# Peripheral_Connections.net
KiCad netlist of a schematic drawn in Altium Designer
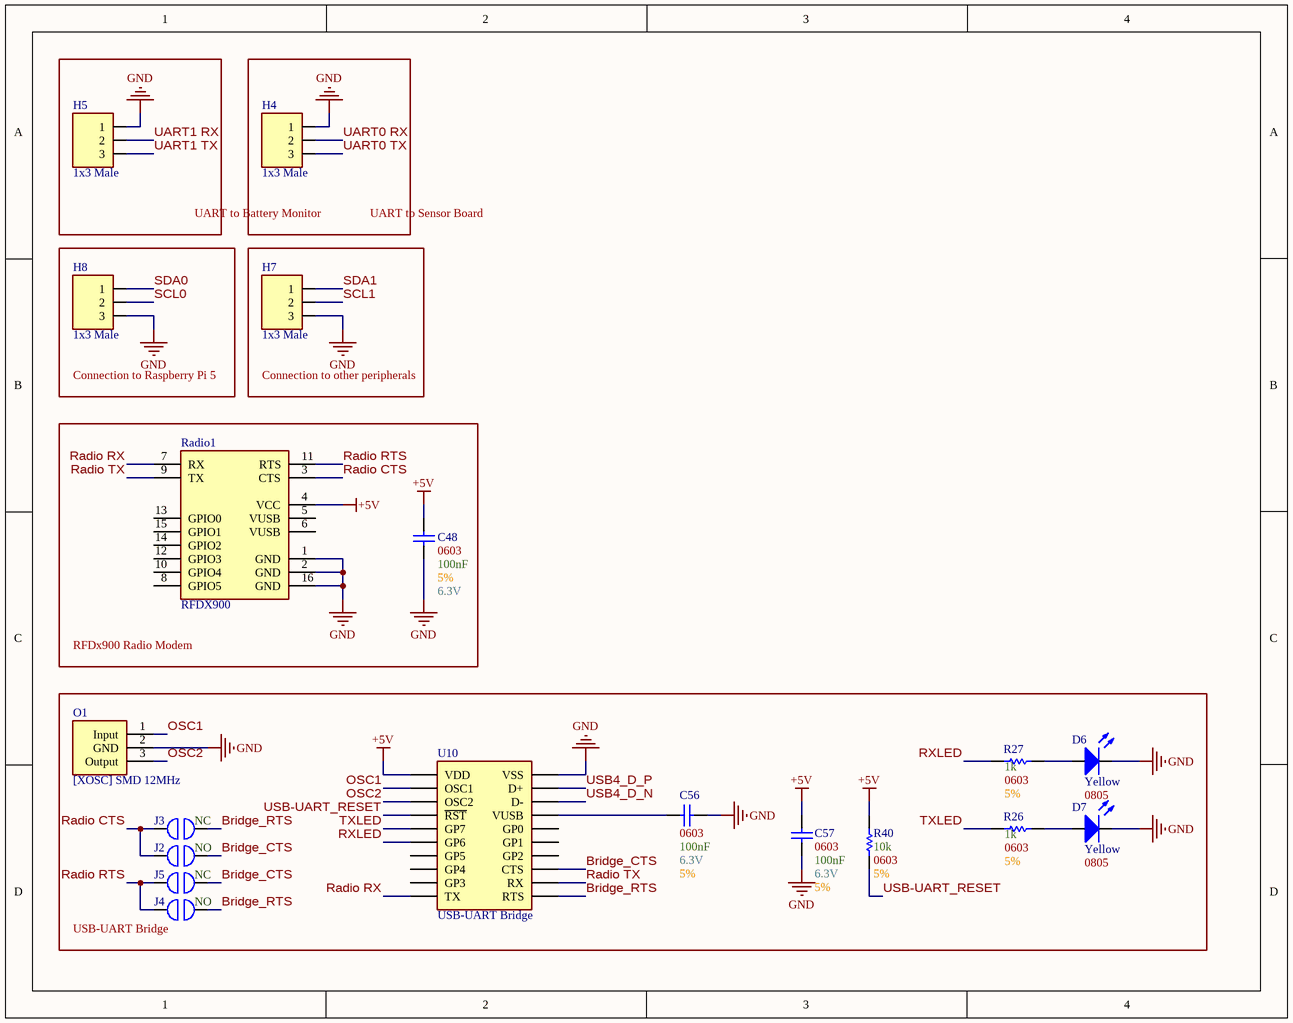
[diagram p0: Peripheral Connections.SchDoc]

(export (version "E")
  (design (tool "Eeschema 10.0.6"))
  (components
    (comp (ref "C48")
      (value "[Cap] SMD Nonpolarized")
      (footprint "[Cap] SMD 0603")
      (fields
        (field (name "SIZE PACKAGE") "0603")
        (field (name "CAPACITANCE") "100nF")
        (field (name "VOLTAGE") "6.3V")
        (field (name "TOLERANCE") "5%")
      )
      (libsource (lib "RADM Components") (part "[Cap] SMD Nonpolarized"))
    )
    (comp (ref "C56")
      (value "[Cap] SMD Nonpolarized")
      (footprint "[Cap] SMD 0603")
      (fields
        (field (name "SIZE PACKAGE") "0603")
        (field (name "CAPACITANCE") "100nF")
        (field (name "VOLTAGE") "6.3V")
        (field (name "TOLERANCE") "5%")
      )
      (libsource (lib "RADM Components") (part "[Cap] SMD Nonpolarized"))
    )
    (comp (ref "C57")
      (value "[Cap] SMD Nonpolarized")
      (footprint "[Cap] SMD 0603")
      (fields
        (field (name "SIZE PACKAGE") "0603")
        (field (name "CAPACITANCE") "100nF")
        (field (name "VOLTAGE") "6.3V")
        (field (name "TOLERANCE") "5%")
      )
      (libsource (lib "RADM Components") (part "[Cap] SMD Nonpolarized"))
    )
    (comp (ref "D6")
      (value "SMD LED")
      (footprint "[LED] SMD 0805")
      (description "Generic")
      (fields (field (name "COLOR") "Yellow") (field (name "SIZE PACKAGE") "0805"))
      (libsource (lib "RADM Components") (part "[LED] SMD"))
    )
    (comp (ref "D7")
      (value "SMD LED")
      (footprint "[LED] SMD 0805")
      (description "Generic")
      (fields (field (name "COLOR") "Yellow") (field (name "SIZE PACKAGE") "0805"))
      (libsource (lib "RADM Components") (part "[LED] SMD"))
    )
    (comp (ref "H4")
      (value "1x3 Male")
      (footprint "[Header] Shrouded 1x3 Male")
      (description "070543-0037\r\nMates with 005057-9403")
      (libsource (lib "RADM Connectors") (part "[Header] Shrouded 1x3 Male"))
    )
    (comp (ref "H5")
      (value "1x3 Male")
      (footprint "[Header] Shrouded 1x3 Male")
      (description "070543-0037\r\nMates with 005057-9403")
      (libsource (lib "RADM Connectors") (part "[Header] Shrouded 1x3 Male"))
    )
    (comp (ref "H7")
      (value "1x3 Male")
      (footprint "[Header] Shrouded 1x3 Male")
      (description "070543-0037\r\nMates with 005057-9403")
      (libsource (lib "RADM Connectors") (part "[Header] Shrouded 1x3 Male"))
    )
    (comp (ref "H8")
      (value "1x3 Male")
      (footprint "[Header] Shrouded 1x3 Male")
      (description "070543-0037\r\nMates with 005057-9403")
      (libsource (lib "RADM Connectors") (part "[Header] Shrouded 1x3 Male"))
    )
    (comp (ref "J2")
      (value "[Jump] SMD Jumper")
      (footprint "[Jumper] Solderable Jumper")
      (description "Solderable jumper")
      (fields (field (name "NO/NC") "NO"))
      (libsource (lib "RADM Components") (part "[Jump] SMD Jumper"))
    )
    (comp (ref "J3")
      (value "[Jump] SMD Jumper")
      (footprint "[Jumper] Solderable Jumper")
      (description "Solderable jumper")
      (fields (field (name "NO/NC") "NC"))
      (libsource (lib "RADM Components") (part "[Jump] SMD Jumper"))
    )
    (comp (ref "J4")
      (value "[Jump] SMD Jumper")
      (footprint "[Jumper] Solderable Jumper")
      (description "Solderable jumper")
      (fields (field (name "NO/NC") "NO"))
      (libsource (lib "RADM Components") (part "[Jump] SMD Jumper"))
    )
    (comp (ref "J5")
      (value "[Jump] SMD Jumper")
      (footprint "[Jumper] Solderable Jumper")
      (description "Solderable jumper")
      (fields (field (name "NO/NC") "NC"))
      (libsource (lib "RADM Components") (part "[Jump] SMD Jumper"))
    )
    (comp (ref "O1")
      (value "[XOSC] SMD 12MHz")
      (footprint "[XOSC] SMD 12MHz")
      (libsource (lib "RADM Components") (part "[XOSC] SMD 12MHz"))
    )
    (comp (ref "R26")
      (value "[Res] SMD Resistor")
      (footprint "[Res] SMD 0603")
      (description "Generic")
      (fields
        (field (name "RESISTANCE") "1k")
        (field (name "SIZE PACKAGE") "0603")
        (field (name "TOLERANCE") "5%")
      )
      (libsource (lib "RADM Components") (part "[Res] SMD Resistor"))
    )
    (comp (ref "R27")
      (value "[Res] SMD Resistor")
      (footprint "[Res] SMD 0603")
      (description "Generic")
      (fields
        (field (name "RESISTANCE") "1k")
        (field (name "SIZE PACKAGE") "0603")
        (field (name "TOLERANCE") "5%")
      )
      (libsource (lib "RADM Components") (part "[Res] SMD Resistor"))
    )
    (comp (ref "R40")
      (value "[Res] SMD Resistor")
      (footprint "[Res] SMD 0603")
      (description "Generic")
      (fields
        (field (name "RESISTANCE") "10k")
        (field (name "SIZE PACKAGE") "0603")
        (field (name "TOLERANCE") "5%")
      )
      (libsource (lib "RADM Components") (part "[Res] SMD Resistor"))
    )
    (comp (ref "Radio1")
      (value "RFDX900")
      (footprint "[Device] RFDX900 Radio SMD Mount")
      (description "RFDX900 Long-Range RF Module")
      (libsource (lib "RADM Components") (part "[Device] RFDX900 Radio"))
    )
    (comp (ref "U10")
      (value "USB-UART Bridge")
      (footprint "[IC] USB-UART Bridge")
      (description "MCP2200T-I/SO")
      (libsource (lib "RADM Components") (part "[IC] USB-UART Bridge"))
    )
  )
  (nets
    (net (code "1") (name "+5V") (class "Default")
      (node (ref "C48") (pin "2") (pinfunction "2_2") (pintype "passive"))
      (node (ref "C57") (pin "2") (pinfunction "2_2") (pintype "passive"))
      (node (ref "R40") (pin "2") (pinfunction "2_2") (pintype "passive"))
      (node (ref "Radio1") (pin "4") (pinfunction "VCC_4") (pintype "passive"))
      (node (ref "U10") (pin "1") (pinfunction "VDD_1") (pintype "passive"))
    )
    (net (code "2") (name "/Bridge_CTS") (class "Default")
      (node (ref "J2") (pin "2") (pintype "passive"))
      (node (ref "J5") (pin "2") (pintype "passive"))
      (node (ref "U10") (pin "13") (pinfunction "CTS_13") (pintype "passive"))
    )
    (net (code "3") (name "/Bridge_RTS") (class "Default")
      (node (ref "J3") (pin "2") (pintype "passive"))
      (node (ref "J4") (pin "2") (pintype "passive"))
      (node (ref "U10") (pin "11") (pinfunction "RTS_11") (pintype "passive"))
    )
    (net (code "4") (name "/OSC1") (class "Default")
      (node (ref "O1") (pin "1") (pinfunction "Input_1") (pintype "passive"))
      (node (ref "U10") (pin "2") (pinfunction "OSC1_2") (pintype "passive"))
    )
    (net (code "5") (name "/OSC2") (class "Default")
      (node (ref "O1") (pin "3") (pinfunction "Output_3") (pintype "passive"))
      (node (ref "U10") (pin "3") (pinfunction "OSC2_3") (pintype "passive"))
    )
    (net (code "6") (name "/RXLED") (class "Default")
      (node (ref "R27") (pin "2") (pinfunction "2_2") (pintype "passive"))
      (node (ref "U10") (pin "6") (pinfunction "GP6_6") (pintype "passive"))
    )
    (net (code "7") (name "/Radio CTS") (class "Default")
      (node (ref "J2") (pin "1") (pintype "passive"))
      (node (ref "J3") (pin "1") (pintype "passive"))
      (node (ref "Radio1") (pin "3") (pinfunction "CTS_3") (pintype "passive"))
    )
    (net (code "8") (name "/Radio RTS") (class "Default")
      (node (ref "J4") (pin "1") (pintype "passive"))
      (node (ref "J5") (pin "1") (pintype "passive"))
      (node (ref "Radio1") (pin "11") (pinfunction "RTS_11") (pintype "passive"))
    )
    (net (code "9") (name "/Radio RX") (class "Default")
      (node (ref "Radio1") (pin "7") (pinfunction "RX_7") (pintype "passive"))
      (node (ref "U10") (pin "10") (pinfunction "TX_10") (pintype "passive"))
    )
    (net (code "10") (name "/Radio TX") (class "Default")
      (node (ref "Radio1") (pin "9") (pinfunction "TX_9") (pintype "passive"))
      (node (ref "U10") (pin "12") (pinfunction "RX_12") (pintype "passive"))
    )
    (net (code "11") (name "/SCL0") (class "Default")
      (node (ref "H8") (pin "2") (pinfunction "2_2") (pintype "passive"))
    )
    (net (code "12") (name "/SCL1") (class "Default")
      (node (ref "H7") (pin "2") (pinfunction "2_2") (pintype "passive"))
    )
    (net (code "13") (name "/SDA0") (class "Default")
      (node (ref "H8") (pin "1") (pinfunction "1_1") (pintype "passive"))
    )
    (net (code "14") (name "/SDA1") (class "Default")
      (node (ref "H7") (pin "1") (pinfunction "1_1") (pintype "passive"))
    )
    (net (code "15") (name "/TXLED") (class "Default")
      (node (ref "R26") (pin "2") (pinfunction "2_2") (pintype "passive"))
      (node (ref "U10") (pin "5") (pinfunction "GP7_5") (pintype "passive"))
    )
    (net (code "16") (name "/UART0 RX") (class "Default")
      (node (ref "H4") (pin "2") (pinfunction "2_2") (pintype "passive"))
    )
    (net (code "17") (name "/UART0 TX") (class "Default")
      (node (ref "H4") (pin "3") (pinfunction "3_3") (pintype "passive"))
    )
    (net (code "18") (name "/UART1 RX") (class "Default")
      (node (ref "H5") (pin "2") (pinfunction "2_2") (pintype "passive"))
    )
    (net (code "19") (name "/UART1 TX") (class "Default")
      (node (ref "H5") (pin "3") (pinfunction "3_3") (pintype "passive"))
    )
    (net (code "20") (name "/USB-UART_RESET") (class "Default")
      (node (ref "R40") (pin "1") (pinfunction "1_1") (pintype "passive"))
      (node (ref "U10") (pin "4") (pinfunction "RST_4") (pintype "passive"))
    )
    (net (code "21") (name "/USB4_D_N") (class "Default")
      (node (ref "U10") (pin "18") (pinfunction "D-_18") (pintype "passive"))
    )
    (net (code "22") (name "/USB4_D_P") (class "Default")
      (node (ref "U10") (pin "19") (pinfunction "D+_19") (pintype "passive"))
    )
    (net (code "23") (name "GND") (class "Default")
      (node (ref "C48") (pin "1") (pinfunction "1_1") (pintype "passive"))
      (node (ref "C56") (pin "1") (pinfunction "1_1") (pintype "passive"))
      (node (ref "C57") (pin "1") (pinfunction "1_1") (pintype "passive"))
      (node (ref "D6") (pin "2") (pinfunction "Cathode_2") (pintype "passive"))
      (node (ref "D7") (pin "2") (pinfunction "Cathode_2") (pintype "passive"))
      (node (ref "H4") (pin "1") (pinfunction "1_1") (pintype "passive"))
      (node (ref "H5") (pin "1") (pinfunction "1_1") (pintype "passive"))
      (node (ref "H7") (pin "3") (pinfunction "3_3") (pintype "passive"))
      (node (ref "H8") (pin "3") (pinfunction "3_3") (pintype "passive"))
      (node (ref "O1") (pin "2") (pinfunction "GND_2") (pintype "passive"))
      (node (ref "Radio1") (pin "1") (pinfunction "GND_1") (pintype "passive"))
      (node (ref "Radio1") (pin "16") (pinfunction "GND_16") (pintype "passive"))
      (node (ref "Radio1") (pin "2") (pinfunction "GND_2") (pintype "passive"))
      (node (ref "U10") (pin "20") (pinfunction "VSS_20") (pintype "passive"))
    )
    (net (code "24") (name "Net-(D6-Anode)") (class "Default")
      (node (ref "D6") (pin "1") (pinfunction "Anode_1") (pintype "passive"))
      (node (ref "R27") (pin "1") (pinfunction "1_1") (pintype "passive"))
    )
    (net (code "25") (name "Net-(D7-Anode)") (class "Default")
      (node (ref "D7") (pin "1") (pinfunction "Anode_1") (pintype "passive"))
      (node (ref "R26") (pin "1") (pinfunction "1_1") (pintype "passive"))
    )
    (net (code "26") (name "Net-(U10-VUSB)") (class "Default")
      (node (ref "C56") (pin "2") (pinfunction "2_2") (pintype "passive"))
      (node (ref "U10") (pin "17") (pinfunction "VUSB_17") (pintype "passive"))
    )
    (net (code "27") (name "unconnected-(Radio1-GPIO0-Pad13)") (class "Default")
      (node (ref "Radio1") (pin "13") (pinfunction "GPIO0_13") (pintype "passive"))
    )
    (net (code "28") (name "unconnected-(Radio1-GPIO1-Pad15)") (class "Default")
      (node (ref "Radio1") (pin "15") (pinfunction "GPIO1_15") (pintype "passive"))
    )
    (net (code "29") (name "unconnected-(Radio1-GPIO2-Pad14)") (class "Default")
      (node (ref "Radio1") (pin "14") (pinfunction "GPIO2_14") (pintype "passive"))
    )
    (net (code "30") (name "unconnected-(Radio1-GPIO3-Pad12)") (class "Default")
      (node (ref "Radio1") (pin "12") (pinfunction "GPIO3_12") (pintype "passive"))
    )
    (net (code "31") (name "unconnected-(Radio1-GPIO4-Pad10)") (class "Default")
      (node (ref "Radio1") (pin "10") (pinfunction "GPIO4_10") (pintype "passive"))
    )
    (net (code "32") (name "unconnected-(Radio1-GPIO5-Pad8)") (class "Default")
      (node (ref "Radio1") (pin "8") (pinfunction "GPIO5_8") (pintype "passive"))
    )
    (net (code "33") (name "unconnected-(Radio1-VUSB-Pad5)") (class "Default")
      (node (ref "Radio1") (pin "5") (pinfunction "VUSB_5") (pintype "passive"))
    )
    (net (code "34") (name "unconnected-(Radio1-VUSB-Pad6)") (class "Default")
      (node (ref "Radio1") (pin "6") (pinfunction "VUSB_6") (pintype "passive"))
    )
    (net (code "35") (name "unconnected-(U10-GP0-Pad16)") (class "Default")
      (node (ref "U10") (pin "16") (pinfunction "GP0_16") (pintype "passive"))
    )
    (net (code "36") (name "unconnected-(U10-GP1-Pad15)") (class "Default")
      (node (ref "U10") (pin "15") (pinfunction "GP1_15") (pintype "passive"))
    )
    (net (code "37") (name "unconnected-(U10-GP2-Pad14)") (class "Default")
      (node (ref "U10") (pin "14") (pinfunction "GP2_14") (pintype "passive"))
    )
    (net (code "38") (name "unconnected-(U10-GP3-Pad9)") (class "Default")
      (node (ref "U10") (pin "9") (pinfunction "GP3_9") (pintype "passive"))
    )
    (net (code "39") (name "unconnected-(U10-GP4-Pad8)") (class "Default")
      (node (ref "U10") (pin "8") (pinfunction "GP4_8") (pintype "passive"))
    )
    (net (code "40") (name "unconnected-(U10-GP5-Pad7)") (class "Default")
      (node (ref "U10") (pin "7") (pinfunction "GP5_7") (pintype "passive"))
    )
  )
)
